# M882.net
KiCad netlist of a schematic drawn in EAGLE
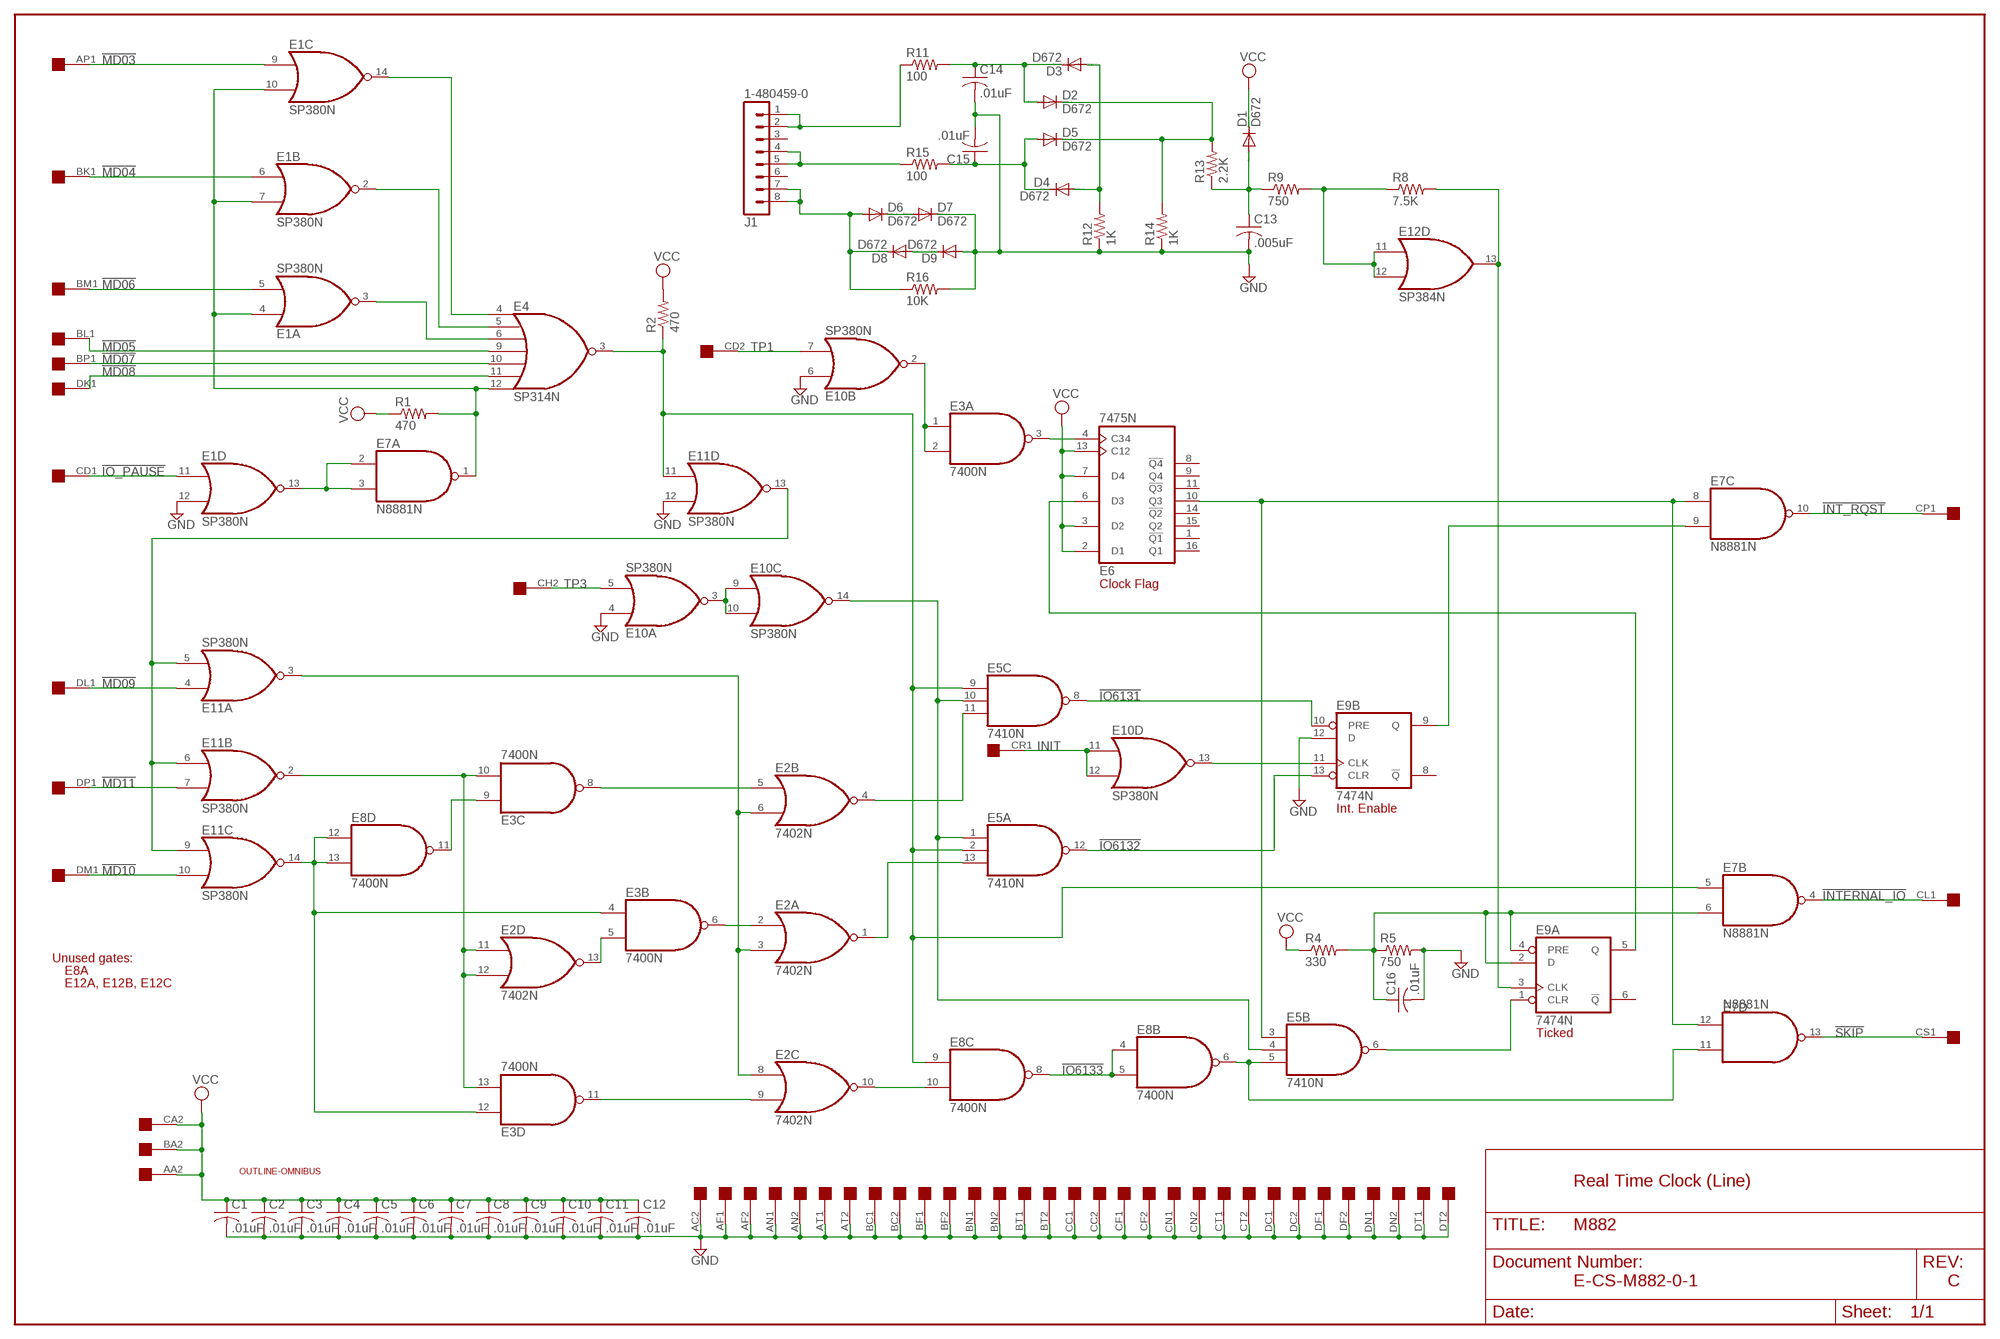
[diagram p0: schematic, sheet 1]

(export (version "E")
  (design (tool "Eeschema 10.0.6"))
  (components
    (comp (ref "C1")
      (value ".01uF")
      (footprint "eagle-import:C050-025X075")
      (libsource (lib "eagle-import") (part "C-US050-025X075"))
    )
    (comp (ref "C2")
      (value ".01uF")
      (footprint "eagle-import:C050-025X075")
      (libsource (lib "eagle-import") (part "C-US050-025X075"))
    )
    (comp (ref "C3")
      (value ".01uF")
      (footprint "eagle-import:C050-025X075")
      (libsource (lib "eagle-import") (part "C-US050-025X075"))
    )
    (comp (ref "C4")
      (value ".01uF")
      (footprint "eagle-import:C050-025X075")
      (libsource (lib "eagle-import") (part "C-US050-025X075"))
    )
    (comp (ref "C5")
      (value ".01uF")
      (footprint "eagle-import:C050-025X075")
      (libsource (lib "eagle-import") (part "C-US050-025X075"))
    )
    (comp (ref "C6")
      (value ".01uF")
      (footprint "eagle-import:C050-025X075")
      (libsource (lib "eagle-import") (part "C-US050-025X075"))
    )
    (comp (ref "C7")
      (value ".01uF")
      (footprint "eagle-import:C050-025X075")
      (libsource (lib "eagle-import") (part "C-US050-025X075"))
    )
    (comp (ref "C8")
      (value ".01uF")
      (footprint "eagle-import:C050-025X075")
      (libsource (lib "eagle-import") (part "C-US050-025X075"))
    )
    (comp (ref "C9")
      (value ".01uF")
      (footprint "eagle-import:C050-025X075")
      (libsource (lib "eagle-import") (part "C-US050-025X075"))
    )
    (comp (ref "C10")
      (value ".01uF")
      (footprint "eagle-import:C050-025X075")
      (libsource (lib "eagle-import") (part "C-US050-025X075"))
    )
    (comp (ref "C11")
      (value ".01uF")
      (footprint "eagle-import:C050-025X075")
      (libsource (lib "eagle-import") (part "C-US050-025X075"))
    )
    (comp (ref "C12")
      (value ".01uF")
      (footprint "eagle-import:C050-025X075")
      (libsource (lib "eagle-import") (part "C-US050-025X075"))
    )
    (comp (ref "C13")
      (value ".005uF")
      (footprint "eagle-import:C050-025X075")
      (libsource (lib "eagle-import") (part "C-US050-025X075"))
    )
    (comp (ref "C14")
      (value ".01uF")
      (footprint "eagle-import:C050-025X075")
      (libsource (lib "eagle-import") (part "C-US050-025X075"))
    )
    (comp (ref "C15")
      (value ".01uF")
      (footprint "eagle-import:C050-025X075")
      (libsource (lib "eagle-import") (part "C-US050-025X075"))
    )
    (comp (ref "C16")
      (value ".01uF")
      (footprint "eagle-import:C050-025X075")
      (libsource (lib "eagle-import") (part "C-US050-025X075"))
    )
    (comp (ref "D1")
      (value "D672")
      (footprint "eagle-import:DO35-10")
      (libsource (lib "eagle-import") (part "1N4148DO35-10"))
    )
    (comp (ref "D2")
      (value "D672")
      (footprint "eagle-import:DO35-10")
      (libsource (lib "eagle-import") (part "1N4148DO35-10"))
    )
    (comp (ref "D3")
      (value "D672")
      (footprint "eagle-import:DO35-10")
      (libsource (lib "eagle-import") (part "1N4148DO35-10"))
    )
    (comp (ref "D4")
      (value "D672")
      (footprint "eagle-import:DO35-10")
      (libsource (lib "eagle-import") (part "1N4148DO35-10"))
    )
    (comp (ref "D5")
      (value "D672")
      (footprint "eagle-import:DO35-10")
      (libsource (lib "eagle-import") (part "1N4148DO35-10"))
    )
    (comp (ref "D6")
      (value "D672")
      (footprint "eagle-import:DO35-10")
      (libsource (lib "eagle-import") (part "1N4148DO35-10"))
    )
    (comp (ref "D7")
      (value "D672")
      (footprint "eagle-import:DO35-10")
      (libsource (lib "eagle-import") (part "1N4148DO35-10"))
    )
    (comp (ref "D8")
      (value "D672")
      (footprint "eagle-import:DO35-10")
      (libsource (lib "eagle-import") (part "1N4148DO35-10"))
    )
    (comp (ref "D9")
      (value "D672")
      (footprint "eagle-import:DO35-10")
      (libsource (lib "eagle-import") (part "1N4148DO35-10"))
    )
    (comp (ref "E1")
      (value "SP380N")
      (footprint "eagle-import:DIL14")
      (libsource (lib "eagle-import") (part "SP380N"))
    )
    (comp (ref "E2")
      (value "7402N")
      (footprint "eagle-import:DIL14")
      (libsource (lib "eagle-import") (part "7402N"))
    )
    (comp (ref "E3")
      (value "7400N")
      (footprint "eagle-import:DIL14")
      (libsource (lib "eagle-import") (part "7400N"))
    )
    (comp (ref "E4")
      (value "SP314N")
      (footprint "eagle-import:DIL14")
      (libsource (lib "eagle-import") (part "SP314N"))
    )
    (comp (ref "E5")
      (value "7410N")
      (footprint "eagle-import:DIL14")
      (libsource (lib "eagle-import") (part "7410N"))
    )
    (comp (ref "E6")
      (value "7475N")
      (footprint "eagle-import:DIL16")
      (libsource (lib "eagle-import") (part "7475N"))
    )
    (comp (ref "E7")
      (value "N8881N")
      (footprint "eagle-import:DIL14")
      (libsource (lib "eagle-import") (part "N8881N"))
    )
    (comp (ref "E8")
      (value "7400N")
      (footprint "eagle-import:DIL14")
      (libsource (lib "eagle-import") (part "7400N"))
    )
    (comp (ref "E9")
      (value "7474N")
      (footprint "eagle-import:DIL14")
      (libsource (lib "eagle-import") (part "7474NS"))
    )
    (comp (ref "E10")
      (value "SP380N")
      (footprint "eagle-import:DIL14")
      (libsource (lib "eagle-import") (part "SP380N"))
    )
    (comp (ref "E11")
      (value "SP380N")
      (footprint "eagle-import:DIL14")
      (libsource (lib "eagle-import") (part "SP380N"))
    )
    (comp (ref "E12")
      (value "SP384N")
      (footprint "eagle-import:DIL14")
      (libsource (lib "eagle-import") (part "SP384N"))
    )
    (comp (ref "EDGE")
      (value "QUAD")
      (footprint "eagle-import:EDGE-CON8")
      (libsource (lib "eagle-import") (part "QUAD"))
    )
    (comp (ref "J1")
      (value "1-480459-0")
      (footprint "eagle-import:1-480459-0")
      (libsource (lib "eagle-import") (part "1-480459-0"))
    )
    (comp (ref "R1")
      (value "470")
      (footprint "eagle-import:0207_10")
      (libsource (lib "eagle-import") (part "R-US_0207/10"))
    )
    (comp (ref "R2")
      (value "470")
      (footprint "eagle-import:0207_10")
      (libsource (lib "eagle-import") (part "R-US_0207/10"))
    )
    (comp (ref "R4")
      (value "330")
      (footprint "eagle-import:0207_10")
      (libsource (lib "eagle-import") (part "R-US_0207/10"))
    )
    (comp (ref "R5")
      (value "750")
      (footprint "eagle-import:0207_10")
      (libsource (lib "eagle-import") (part "R-US_0207/10"))
    )
    (comp (ref "R8")
      (value "7.5K")
      (footprint "eagle-import:0207_10")
      (libsource (lib "eagle-import") (part "R-US_0207/10"))
    )
    (comp (ref "R9")
      (value "750")
      (footprint "eagle-import:0207_10")
      (libsource (lib "eagle-import") (part "R-US_0207/10"))
    )
    (comp (ref "R11")
      (value "100")
      (footprint "eagle-import:0207_10")
      (libsource (lib "eagle-import") (part "R-US_0207/10"))
    )
    (comp (ref "R12")
      (value "1K")
      (footprint "eagle-import:0207_10")
      (libsource (lib "eagle-import") (part "R-US_0207/10"))
    )
    (comp (ref "R13")
      (value "2.2K")
      (footprint "eagle-import:0207_10")
      (libsource (lib "eagle-import") (part "R-US_0207/10"))
    )
    (comp (ref "R14")
      (value "1K")
      (footprint "eagle-import:0207_10")
      (libsource (lib "eagle-import") (part "R-US_0207/10"))
    )
    (comp (ref "R15")
      (value "100")
      (footprint "eagle-import:0207_10")
      (libsource (lib "eagle-import") (part "R-US_0207/10"))
    )
    (comp (ref "R16")
      (value "10K")
      (footprint "eagle-import:0207_10")
      (libsource (lib "eagle-import") (part "R-US_0207/10"))
    )
    (comp (ref "U$1")
      (value "OUTLINE-OMNIBUS")
      (footprint "eagle-import:OMNIBUS")
      (libsource (lib "eagle-import") (part "OUTLINE-OMNIBUS"))
    )
  )
  (nets
    (net (code "1") (name "/INIT") (class "Default")
      (node (ref "E10") (pin "11") (pinfunction "I0_11") (pintype "input"))
      (node (ref "E10") (pin "12") (pinfunction "I1_12") (pintype "input"))
      (node (ref "EDGE") (pin "CR1") (pinfunction "1_CR1") (pintype "bidirectional"))
    )
    (net (code "2") (name "/TP1") (class "Default")
      (node (ref "E10") (pin "7") (pinfunction "I1_7") (pintype "input"))
      (node (ref "EDGE") (pin "CD2") (pinfunction "1_CD2") (pintype "bidirectional"))
    )
    (net (code "3") (name "/TP3") (class "Default")
      (node (ref "E10") (pin "5") (pinfunction "I1_5") (pintype "input"))
      (node (ref "EDGE") (pin "CH2") (pinfunction "1_CH2") (pintype "bidirectional"))
    )
    (net (code "4") (name "/~{INTERNAL_IO}") (class "Default")
      (node (ref "E7") (pin "4") (pinfunction "O_4") (pintype "open_collector"))
      (node (ref "EDGE") (pin "CL1") (pinfunction "1_CL1") (pintype "bidirectional"))
    )
    (net (code "5") (name "/~{INT_RQST}") (class "Default")
      (node (ref "E7") (pin "10") (pinfunction "O_10") (pintype "open_collector"))
      (node (ref "EDGE") (pin "CP1") (pinfunction "1_CP1") (pintype "bidirectional"))
    )
    (net (code "6") (name "/~{IO6131}") (class "Default")
      (node (ref "E5") (pin "8") (pinfunction "O_8") (pintype "output"))
      (node (ref "E9") (pin "10") (pinfunction "PRE_10") (pintype "input"))
    )
    (net (code "7") (name "/~{IO6132}") (class "Default")
      (node (ref "E5") (pin "12") (pinfunction "O_12") (pintype "output"))
      (node (ref "E9") (pin "13") (pinfunction "CLR_13") (pintype "input"))
    )
    (net (code "8") (name "/~{IO6133}") (class "Default")
      (node (ref "E8") (pin "4") (pinfunction "I0_4") (pintype "input"))
      (node (ref "E8") (pin "5") (pinfunction "I1_5") (pintype "input"))
      (node (ref "E8") (pin "8") (pinfunction "O_8") (pintype "output"))
    )
    (net (code "9") (name "/~{IO_PAUSE}") (class "Default")
      (node (ref "E1") (pin "11") (pinfunction "I0_11") (pintype "input"))
      (node (ref "EDGE") (pin "CD1") (pinfunction "1_CD1") (pintype "bidirectional"))
    )
    (net (code "10") (name "/~{MD03}") (class "Default")
      (node (ref "E1") (pin "9") (pinfunction "I0_9") (pintype "input"))
      (node (ref "EDGE") (pin "AP1") (pinfunction "1_AP1") (pintype "bidirectional"))
    )
    (net (code "11") (name "/~{MD04}") (class "Default")
      (node (ref "E1") (pin "6") (pinfunction "I0_6") (pintype "input"))
      (node (ref "EDGE") (pin "BK1") (pinfunction "1_BK1") (pintype "bidirectional"))
    )
    (net (code "12") (name "/~{MD05}") (class "Default")
      (node (ref "E4") (pin "9") (pinfunction "I3_9") (pintype "input"))
      (node (ref "EDGE") (pin "BL1") (pinfunction "1_BL1") (pintype "bidirectional"))
    )
    (net (code "13") (name "/~{MD06}") (class "Default")
      (node (ref "E1") (pin "5") (pinfunction "I1_5") (pintype "input"))
      (node (ref "EDGE") (pin "BM1") (pinfunction "1_BM1") (pintype "bidirectional"))
    )
    (net (code "14") (name "/~{MD07}") (class "Default")
      (node (ref "E4") (pin "10") (pinfunction "I4_10") (pintype "input"))
      (node (ref "EDGE") (pin "BP1") (pinfunction "1_BP1") (pintype "bidirectional"))
    )
    (net (code "15") (name "/~{MD08}") (class "Default")
      (node (ref "E4") (pin "11") (pinfunction "I5_11") (pintype "input"))
      (node (ref "EDGE") (pin "DK1") (pinfunction "1_DK1") (pintype "bidirectional"))
    )
    (net (code "16") (name "/~{MD09}") (class "Default")
      (node (ref "E11") (pin "4") (pinfunction "I0_4") (pintype "input"))
      (node (ref "EDGE") (pin "DL1") (pinfunction "1_DL1") (pintype "bidirectional"))
    )
    (net (code "17") (name "/~{MD10}") (class "Default")
      (node (ref "E11") (pin "10") (pinfunction "I1_10") (pintype "input"))
      (node (ref "EDGE") (pin "DM1") (pinfunction "1_DM1") (pintype "bidirectional"))
    )
    (net (code "18") (name "/~{MD11}") (class "Default")
      (node (ref "E11") (pin "7") (pinfunction "I1_7") (pintype "input"))
      (node (ref "EDGE") (pin "DP1") (pinfunction "1_DP1") (pintype "bidirectional"))
    )
    (net (code "19") (name "/~{SKIP}") (class "Default")
      (node (ref "E7") (pin "13") (pinfunction "O_13") (pintype "open_collector"))
      (node (ref "EDGE") (pin "CS1") (pinfunction "1_CS1") (pintype "bidirectional"))
    )
    (net (code "20") (name "GND") (class "Default")
      (node (ref "C1") (pin "2") (pinfunction "2_2") (pintype "passive"))
      (node (ref "C10") (pin "2") (pinfunction "2_2") (pintype "passive"))
      (node (ref "C11") (pin "2") (pinfunction "2_2") (pintype "passive"))
      (node (ref "C12") (pin "2") (pinfunction "2_2") (pintype "passive"))
      (node (ref "C13") (pin "2") (pinfunction "2_2") (pintype "passive"))
      (node (ref "C14") (pin "2") (pinfunction "2_2") (pintype "passive"))
      (node (ref "C15") (pin "2") (pinfunction "2_2") (pintype "passive"))
      (node (ref "C16") (pin "2") (pinfunction "2_2") (pintype "passive"))
      (node (ref "C2") (pin "2") (pinfunction "2_2") (pintype "passive"))
      (node (ref "C3") (pin "2") (pinfunction "2_2") (pintype "passive"))
      (node (ref "C4") (pin "2") (pinfunction "2_2") (pintype "passive"))
      (node (ref "C5") (pin "2") (pinfunction "2_2") (pintype "passive"))
      (node (ref "C6") (pin "2") (pinfunction "2_2") (pintype "passive"))
      (node (ref "C7") (pin "2") (pinfunction "2_2") (pintype "passive"))
      (node (ref "C8") (pin "2") (pinfunction "2_2") (pintype "passive"))
      (node (ref "C9") (pin "2") (pinfunction "2_2") (pintype "passive"))
      (node (ref "D7") (pin "C") (pinfunction "C_C") (pintype "passive"))
      (node (ref "D9") (pin "A") (pinfunction "A_A") (pintype "passive"))
      (node (ref "E1") (pin "12") (pinfunction "I1_12") (pintype "input"))
      (node (ref "E10") (pin "4") (pinfunction "I0_4") (pintype "input"))
      (node (ref "E10") (pin "6") (pinfunction "I0_6") (pintype "input"))
      (node (ref "E11") (pin "12") (pinfunction "I1_12") (pintype "input"))
      (node (ref "E9") (pin "12") (pinfunction "D_12") (pintype "input"))
      (node (ref "EDGE") (pin "AC2") (pinfunction "1_AC2") (pintype "bidirectional"))
      (node (ref "EDGE") (pin "AF1") (pinfunction "1_AF1") (pintype "bidirectional"))
      (node (ref "EDGE") (pin "AF2") (pinfunction "1_AF2") (pintype "bidirectional"))
      (node (ref "EDGE") (pin "AN1") (pinfunction "1_AN1") (pintype "bidirectional"))
      (node (ref "EDGE") (pin "AN2") (pinfunction "1_AN2") (pintype "bidirectional"))
      (node (ref "EDGE") (pin "AT1") (pinfunction "1_AT1") (pintype "bidirectional"))
      (node (ref "EDGE") (pin "AT2") (pinfunction "1_AT2") (pintype "bidirectional"))
      (node (ref "EDGE") (pin "BC1") (pinfunction "1_BC1") (pintype "bidirectional"))
      (node (ref "EDGE") (pin "BC2") (pinfunction "1_BC2") (pintype "bidirectional"))
      (node (ref "EDGE") (pin "BF1") (pinfunction "1_BF1") (pintype "bidirectional"))
      (node (ref "EDGE") (pin "BF2") (pinfunction "1_BF2") (pintype "bidirectional"))
      (node (ref "EDGE") (pin "BN1") (pinfunction "1_BN1") (pintype "bidirectional"))
      (node (ref "EDGE") (pin "BN2") (pinfunction "1_BN2") (pintype "bidirectional"))
      (node (ref "EDGE") (pin "BT1") (pinfunction "1_BT1") (pintype "bidirectional"))
      (node (ref "EDGE") (pin "BT2") (pinfunction "1_BT2") (pintype "bidirectional"))
      (node (ref "EDGE") (pin "CC1") (pinfunction "1_CC1") (pintype "bidirectional"))
      (node (ref "EDGE") (pin "CC2") (pinfunction "1_CC2") (pintype "bidirectional"))
      (node (ref "EDGE") (pin "CF1") (pinfunction "1_CF1") (pintype "bidirectional"))
      (node (ref "EDGE") (pin "CF2") (pinfunction "1_CF2") (pintype "bidirectional"))
      (node (ref "EDGE") (pin "CN1") (pinfunction "1_CN1") (pintype "bidirectional"))
      (node (ref "EDGE") (pin "CN2") (pinfunction "1_CN2") (pintype "bidirectional"))
      (node (ref "EDGE") (pin "CT1") (pinfunction "1_CT1") (pintype "bidirectional"))
      (node (ref "EDGE") (pin "CT2") (pinfunction "1_CT2") (pintype "bidirectional"))
      (node (ref "EDGE") (pin "DC1") (pinfunction "1_DC1") (pintype "bidirectional"))
      (node (ref "EDGE") (pin "DC2") (pinfunction "1_DC2") (pintype "bidirectional"))
      (node (ref "EDGE") (pin "DF1") (pinfunction "1_DF1") (pintype "bidirectional"))
      (node (ref "EDGE") (pin "DF2") (pinfunction "1_DF2") (pintype "bidirectional"))
      (node (ref "EDGE") (pin "DN1") (pinfunction "1_DN1") (pintype "bidirectional"))
      (node (ref "EDGE") (pin "DN2") (pinfunction "1_DN2") (pintype "bidirectional"))
      (node (ref "EDGE") (pin "DT1") (pinfunction "1_DT1") (pintype "bidirectional"))
      (node (ref "EDGE") (pin "DT2") (pinfunction "1_DT2") (pintype "bidirectional"))
      (node (ref "R12") (pin "1") (pinfunction "1_1") (pintype "passive"))
      (node (ref "R14") (pin "1") (pinfunction "1_1") (pintype "passive"))
      (node (ref "R16") (pin "2") (pinfunction "2_2") (pintype "passive"))
      (node (ref "R5") (pin "2") (pinfunction "2_2") (pintype "passive"))
    )
    (net (code "21") (name "Net-(C13-Pad1)") (class "Default")
      (node (ref "C13") (pin "1") (pinfunction "1_1") (pintype "passive"))
      (node (ref "D1") (pin "A") (pinfunction "A_A") (pintype "passive"))
      (node (ref "R13") (pin "1") (pinfunction "1_1") (pintype "passive"))
      (node (ref "R9") (pin "1") (pinfunction "1_1") (pintype "passive"))
    )
    (net (code "22") (name "Net-(C14-Pad1)") (class "Default")
      (node (ref "C14") (pin "1") (pinfunction "1_1") (pintype "passive"))
      (node (ref "D2") (pin "A") (pinfunction "A_A") (pintype "passive"))
      (node (ref "D3") (pin "C") (pinfunction "C_C") (pintype "passive"))
      (node (ref "R11") (pin "2") (pinfunction "2_2") (pintype "passive"))
    )
    (net (code "23") (name "Net-(C15-Pad1)") (class "Default")
      (node (ref "C15") (pin "1") (pinfunction "1_1") (pintype "passive"))
      (node (ref "D4") (pin "C") (pinfunction "C_C") (pintype "passive"))
      (node (ref "D5") (pin "A") (pinfunction "A_A") (pintype "passive"))
      (node (ref "R15") (pin "2") (pinfunction "2_2") (pintype "passive"))
    )
    (net (code "24") (name "Net-(D2-PadC)") (class "Default")
      (node (ref "D2") (pin "C") (pinfunction "C_C") (pintype "passive"))
      (node (ref "D5") (pin "C") (pinfunction "C_C") (pintype "passive"))
      (node (ref "R13") (pin "2") (pinfunction "2_2") (pintype "passive"))
      (node (ref "R14") (pin "2") (pinfunction "2_2") (pintype "passive"))
    )
    (net (code "25") (name "Net-(D3-PadA)") (class "Default")
      (node (ref "D3") (pin "A") (pinfunction "A_A") (pintype "passive"))
      (node (ref "D4") (pin "A") (pinfunction "A_A") (pintype "passive"))
      (node (ref "R12") (pin "2") (pinfunction "2_2") (pintype "passive"))
    )
    (net (code "26") (name "Net-(D6-PadA)") (class "Default")
      (node (ref "D6") (pin "A") (pinfunction "A_A") (pintype "passive"))
      (node (ref "D8") (pin "C") (pinfunction "C_C") (pintype "passive"))
      (node (ref "J1") (pin "7") (pinfunction "7_7") (pintype "passive"))
      (node (ref "J1") (pin "8") (pinfunction "8_8") (pintype "passive"))
      (node (ref "R16") (pin "1") (pinfunction "1_1") (pintype "passive"))
    )
    (net (code "27") (name "Net-(D6-PadC)") (class "Default")
      (node (ref "D6") (pin "C") (pinfunction "C_C") (pintype "passive"))
      (node (ref "D7") (pin "A") (pinfunction "A_A") (pintype "passive"))
    )
    (net (code "28") (name "Net-(D8-PadA)") (class "Default")
      (node (ref "D8") (pin "A") (pinfunction "A_A") (pintype "passive"))
      (node (ref "D9") (pin "C") (pinfunction "C_C") (pintype "passive"))
    )
    (net (code "29") (name "Net-(E1A-I0)") (class "Default")
      (node (ref "E1") (pin "10") (pinfunction "I1_10") (pintype "input"))
      (node (ref "E1") (pin "4") (pinfunction "I0_4") (pintype "input"))
      (node (ref "E1") (pin "7") (pinfunction "I1_7") (pintype "input"))
      (node (ref "E4") (pin "12") (pinfunction "I6_12") (pintype "input"))
      (node (ref "E7") (pin "1") (pinfunction "O_1") (pintype "open_collector"))
      (node (ref "R1") (pin "2") (pinfunction "2_2") (pintype "passive"))
    )
    (net (code "30") (name "Net-(E1A-O)") (class "Default")
      (node (ref "E1") (pin "3") (pinfunction "O_3") (pintype "output"))
      (node (ref "E4") (pin "6") (pinfunction "I2_6") (pintype "input"))
    )
    (net (code "31") (name "Net-(E1B-O)") (class "Default")
      (node (ref "E1") (pin "2") (pinfunction "O_2") (pintype "output"))
      (node (ref "E4") (pin "5") (pinfunction "I1_5") (pintype "input"))
    )
    (net (code "32") (name "Net-(E1C-O)") (class "Default")
      (node (ref "E1") (pin "14") (pinfunction "O_14") (pintype "output"))
      (node (ref "E4") (pin "4") (pinfunction "I0_4") (pintype "input"))
    )
    (net (code "33") (name "Net-(E1D-O)") (class "Default")
      (node (ref "E1") (pin "13") (pinfunction "O_13") (pintype "output"))
      (node (ref "E7") (pin "2") (pinfunction "I0_2") (pintype "input"))
      (node (ref "E7") (pin "3") (pinfunction "I1_3") (pintype "input"))
    )
    (net (code "34") (name "Net-(E2A-I0)") (class "Default")
      (node (ref "E2") (pin "2") (pinfunction "I0_2") (pintype "input"))
      (node (ref "E3") (pin "6") (pinfunction "O_6") (pintype "output"))
    )
    (net (code "35") (name "Net-(E2A-O)") (class "Default")
      (node (ref "E2") (pin "1") (pinfunction "O_1") (pintype "output"))
      (node (ref "E5") (pin "13") (pinfunction "I2_13") (pintype "input"))
    )
    (net (code "36") (name "Net-(E2B-I0)") (class "Default")
      (node (ref "E2") (pin "5") (pinfunction "I0_5") (pintype "input"))
      (node (ref "E3") (pin "8") (pinfunction "O_8") (pintype "output"))
    )
    (net (code "37") (name "Net-(E2B-O)") (class "Default")
      (node (ref "E2") (pin "4") (pinfunction "O_4") (pintype "output"))
      (node (ref "E5") (pin "11") (pinfunction "I2_11") (pintype "input"))
    )
    (net (code "38") (name "Net-(E2C-I1)") (class "Default")
      (node (ref "E2") (pin "9") (pinfunction "I1_9") (pintype "input"))
      (node (ref "E3") (pin "11") (pinfunction "O_11") (pintype "output"))
    )
    (net (code "39") (name "Net-(E2C-O)") (class "Default")
      (node (ref "E2") (pin "10") (pinfunction "O_10") (pintype "output"))
      (node (ref "E8") (pin "10") (pinfunction "I1_10") (pintype "input"))
    )
    (net (code "40") (name "Net-(E2D-O)") (class "Default")
      (node (ref "E2") (pin "13") (pinfunction "O_13") (pintype "output"))
      (node (ref "E3") (pin "5") (pinfunction "I1_5") (pintype "input"))
    )
    (net (code "41") (name "Net-(E3A-O)") (class "Default")
      (node (ref "E3") (pin "3") (pinfunction "O_3") (pintype "output"))
      (node (ref "E6") (pin "4") (pinfunction "C34_4") (pintype "input"))
    )
    (net (code "42") (name "Net-(E3C-I0)") (class "Default")
      (node (ref "E3") (pin "9") (pinfunction "I0_9") (pintype "input"))
      (node (ref "E8") (pin "11") (pinfunction "O_11") (pintype "output"))
    )
    (net (code "43") (name "Net-(E5B-I0)") (class "Default")
      (node (ref "E5") (pin "3") (pinfunction "I0_3") (pintype "input"))
      (node (ref "E6") (pin "10") (pinfunction "Q3_10") (pintype "output"))
      (node (ref "E7") (pin "12") (pinfunction "I1_12") (pintype "input"))
      (node (ref "E7") (pin "8") (pinfunction "I0_8") (pintype "input"))
    )
    (net (code "44") (name "Net-(E5B-I2)") (class "Default")
      (node (ref "E5") (pin "5") (pinfunction "I2_5") (pintype "input"))
      (node (ref "E7") (pin "11") (pinfunction "I0_11") (pintype "input"))
      (node (ref "E8") (pin "6") (pinfunction "O_6") (pintype "output"))
    )
    (net (code "45") (name "Net-(E5B-O)") (class "Default")
      (node (ref "E5") (pin "6") (pinfunction "O_6") (pintype "output"))
      (node (ref "E9") (pin "1") (pinfunction "CLR_1") (pintype "input"))
    )
    (net (code "46") (name "Net-(E6A-D3)") (class "Default")
      (node (ref "E6") (pin "6") (pinfunction "D3_6") (pintype "input"))
      (node (ref "E9") (pin "5") (pinfunction "Q_5") (pintype "output"))
    )
    (net (code "47") (name "Net-(E7B-I1)") (class "Default")
      (node (ref "C16") (pin "1") (pinfunction "1_1") (pintype "passive"))
      (node (ref "E7") (pin "6") (pinfunction "I1_6") (pintype "input"))
      (node (ref "E9") (pin "2") (pinfunction "D_2") (pintype "input"))
      (node (ref "E9") (pin "4") (pinfunction "PRE_4") (pintype "input"))
      (node (ref "R4") (pin "2") (pinfunction "2_2") (pintype "passive"))
      (node (ref "R5") (pin "1") (pinfunction "1_1") (pintype "passive"))
    )
    (net (code "48") (name "Net-(E7C-I1)") (class "Default")
      (node (ref "E7") (pin "9") (pinfunction "I1_9") (pintype "input"))
      (node (ref "E9") (pin "9") (pinfunction "Q_9") (pintype "output"))
    )
    (net (code "49") (name "Net-(E10A-O)") (class "Default")
      (node (ref "E10") (pin "10") (pinfunction "I1_10") (pintype "input"))
      (node (ref "E10") (pin "3") (pinfunction "O_3") (pintype "output"))
      (node (ref "E10") (pin "9") (pinfunction "I0_9") (pintype "input"))
    )
    (net (code "50") (name "Net-(E10B-O)") (class "Default")
      (node (ref "E10") (pin "2") (pinfunction "O_2") (pintype "output"))
      (node (ref "E3") (pin "1") (pinfunction "I0_1") (pintype "input"))
      (node (ref "E3") (pin "2") (pinfunction "I1_2") (pintype "input"))
    )
    (net (code "51") (name "Net-(E10C-O)") (class "Default")
      (node (ref "E10") (pin "14") (pinfunction "O_14") (pintype "output"))
      (node (ref "E5") (pin "1") (pinfunction "I0_1") (pintype "input"))
      (node (ref "E5") (pin "10") (pinfunction "I1_10") (pintype "input"))
      (node (ref "E5") (pin "4") (pinfunction "I1_4") (pintype "input"))
    )
    (net (code "52") (name "Net-(E10D-O)") (class "Default")
      (node (ref "E10") (pin "13") (pinfunction "O_13") (pintype "output"))
      (node (ref "E9") (pin "11") (pinfunction "CLK_11") (pintype "input"))
    )
    (net (code "53") (name "Net-(E11A-I1)") (class "Default")
      (node (ref "E11") (pin "13") (pinfunction "O_13") (pintype "output"))
      (node (ref "E11") (pin "5") (pinfunction "I1_5") (pintype "input"))
      (node (ref "E11") (pin "6") (pinfunction "I0_6") (pintype "input"))
      (node (ref "E11") (pin "9") (pinfunction "I0_9") (pintype "input"))
    )
    (net (code "54") (name "Net-(E11A-O)") (class "Default")
      (node (ref "E11") (pin "3") (pinfunction "O_3") (pintype "output"))
      (node (ref "E2") (pin "3") (pinfunction "I1_3") (pintype "input"))
      (node (ref "E2") (pin "6") (pinfunction "I1_6") (pintype "input"))
      (node (ref "E2") (pin "8") (pinfunction "I0_8") (pintype "input"))
    )
    (net (code "55") (name "Net-(E11B-O)") (class "Default")
      (node (ref "E11") (pin "2") (pinfunction "O_2") (pintype "output"))
      (node (ref "E2") (pin "11") (pinfunction "I0_11") (pintype "input"))
      (node (ref "E2") (pin "12") (pinfunction "I1_12") (pintype "input"))
      (node (ref "E3") (pin "10") (pinfunction "I1_10") (pintype "input"))
      (node (ref "E3") (pin "13") (pinfunction "I1_13") (pintype "input"))
    )
    (net (code "56") (name "Net-(E11C-O)") (class "Default")
      (node (ref "E11") (pin "14") (pinfunction "O_14") (pintype "output"))
      (node (ref "E3") (pin "12") (pinfunction "I0_12") (pintype "input"))
      (node (ref "E3") (pin "4") (pinfunction "I0_4") (pintype "input"))
      (node (ref "E8") (pin "12") (pinfunction "I0_12") (pintype "input"))
      (node (ref "E8") (pin "13") (pinfunction "I1_13") (pintype "input"))
    )
    (net (code "57") (name "Net-(E11D-I0)") (class "Default")
      (node (ref "E11") (pin "11") (pinfunction "I0_11") (pintype "input"))
      (node (ref "E4") (pin "3") (pinfunction "O_3") (pintype "output"))
      (node (ref "E5") (pin "2") (pinfunction "I1_2") (pintype "input"))
      (node (ref "E5") (pin "9") (pinfunction "I0_9") (pintype "input"))
      (node (ref "E7") (pin "5") (pinfunction "I0_5") (pintype "input"))
      (node (ref "E8") (pin "9") (pinfunction "I0_9") (pintype "input"))
      (node (ref "R2") (pin "1") (pinfunction "1_1") (pintype "passive"))
    )
    (net (code "58") (name "Net-(E12D-I0)") (class "Default")
      (node (ref "E12") (pin "11") (pinfunction "I0_11") (pintype "input"))
      (node (ref "E12") (pin "12") (pinfunction "I1_12") (pintype "input"))
      (node (ref "R8") (pin "1") (pinfunction "1_1") (pintype "passive"))
      (node (ref "R9") (pin "2") (pinfunction "2_2") (pintype "passive"))
    )
    (net (code "59") (name "Net-(E12D-O)") (class "Default")
      (node (ref "E12") (pin "13") (pinfunction "O_13") (pintype "output"))
      (node (ref "E9") (pin "3") (pinfunction "CLK_3") (pintype "input"))
      (node (ref "R8") (pin "2") (pinfunction "2_2") (pintype "passive"))
    )
    (net (code "60") (name "Net-(J1-Pad1)") (class "Default")
      (node (ref "J1") (pin "1") (pinfunction "1_1") (pintype "passive"))
      (node (ref "J1") (pin "2") (pinfunction "2_2") (pintype "passive"))
      (node (ref "R11") (pin "1") (pinfunction "1_1") (pintype "passive"))
    )
    (net (code "61") (name "Net-(J1-Pad4)") (class "Default")
      (node (ref "J1") (pin "4") (pinfunction "4_4") (pintype "passive"))
      (node (ref "J1") (pin "5") (pinfunction "5_5") (pintype "passive"))
      (node (ref "R15") (pin "1") (pinfunction "1_1") (pintype "passive"))
    )
    (net (code "62") (name "VCC") (class "Default")
      (node (ref "C1") (pin "1") (pinfunction "1_1") (pintype "passive"))
      (node (ref "C10") (pin "1") (pinfunction "1_1") (pintype "passive"))
      (node (ref "C11") (pin "1") (pinfunction "1_1") (pintype "passive"))
      (node (ref "C12") (pin "1") (pinfunction "1_1") (pintype "passive"))
      (node (ref "C2") (pin "1") (pinfunction "1_1") (pintype "passive"))
      (node (ref "C3") (pin "1") (pinfunction "1_1") (pintype "passive"))
      (node (ref "C4") (pin "1") (pinfunction "1_1") (pintype "passive"))
      (node (ref "C5") (pin "1") (pinfunction "1_1") (pintype "passive"))
      (node (ref "C6") (pin "1") (pinfunction "1_1") (pintype "passive"))
      (node (ref "C7") (pin "1") (pinfunction "1_1") (pintype "passive"))
      (node (ref "C8") (pin "1") (pinfunction "1_1") (pintype "passive"))
      (node (ref "C9") (pin "1") (pinfunction "1_1") (pintype "passive"))
      (node (ref "D1") (pin "C") (pinfunction "C_C") (pintype "passive"))
      (node (ref "E6") (pin "13") (pinfunction "C12_13") (pintype "input"))
      (node (ref "E6") (pin "2") (pinfunction "D1_2") (pintype "input"))
      (node (ref "E6") (pin "3") (pinfunction "D2_3") (pintype "input"))
      (node (ref "E6") (pin "7") (pinfunction "D4_7") (pintype "input"))
      (node (ref "EDGE") (pin "AA2") (pinfunction "1_AA2") (pintype "bidirectional"))
      (node (ref "EDGE") (pin "BA2") (pinfunction "1_BA2") (pintype "bidirectional"))
      (node (ref "EDGE") (pin "CA2") (pinfunction "1_CA2") (pintype "bidirectional"))
      (node (ref "R1") (pin "1") (pinfunction "1_1") (pintype "passive"))
      (node (ref "R2") (pin "2") (pinfunction "2_2") (pintype "passive"))
      (node (ref "R4") (pin "1") (pinfunction "1_1") (pintype "passive"))
    )
    (net (code "63") (name "unconnected-(E6A-Q1-Pad16)") (class "Default")
      (node (ref "E6") (pin "16") (pinfunction "Q1_16") (pintype "output"))
    )
    (net (code "64") (name "unconnected-(E6A-Q2-Pad15)") (class "Default")
      (node (ref "E6") (pin "15") (pinfunction "Q2_15") (pintype "output"))
    )
    (net (code "65") (name "unconnected-(E6A-Q4-Pad9)") (class "Default")
      (node (ref "E6") (pin "9") (pinfunction "Q4_9") (pintype "output"))
    )
    (net (code "66") (name "unconnected-(E6A-~{Q1}-Pad1)") (class "Default")
      (node (ref "E6") (pin "1") (pinfunction "~{Q1}_1") (pintype "output"))
    )
    (net (code "67") (name "unconnected-(E6A-~{Q2}-Pad14)") (class "Default")
      (node (ref "E6") (pin "14") (pinfunction "~{Q2}_14") (pintype "output"))
    )
    (net (code "68") (name "unconnected-(E6A-~{Q3}-Pad11)") (class "Default")
      (node (ref "E6") (pin "11") (pinfunction "~{Q3}_11") (pintype "output"))
    )
    (net (code "69") (name "unconnected-(E6A-~{Q4}-Pad8)") (class "Default")
      (node (ref "E6") (pin "8") (pinfunction "~{Q4}_8") (pintype "output"))
    )
    (net (code "70") (name "unconnected-(E9A-~{Q}-Pad6)") (class "Default")
      (node (ref "E9") (pin "6") (pinfunction "~{Q}_6") (pintype "output"))
    )
    (net (code "71") (name "unconnected-(E9B-~{Q}-Pad8)") (class "Default")
      (node (ref "E9") (pin "8") (pinfunction "~{Q}_8") (pintype "output"))
    )
    (net (code "72") (name "unconnected-(J1-Pad3)") (class "Default")
      (node (ref "J1") (pin "3") (pinfunction "3_3") (pintype "passive"))
    )
    (net (code "73") (name "unconnected-(J1-Pad6)") (class "Default")
      (node (ref "J1") (pin "6") (pinfunction "6_6") (pintype "passive"))
    )
  )
)
